# 1_P1_schdoc.net
KiCad netlist of a schematic drawn in Altium Designer
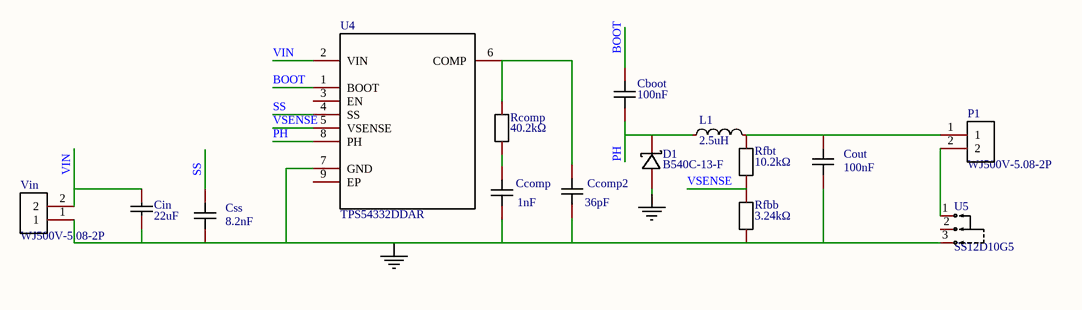
[diagram p0: 1_P1.schdoc.schdoc]

(export (version "E")
  (design (tool "Eeschema 10.0.6"))
  (components
    (comp (ref "Cboot")
      (value "100nF")
      (fields
        (field (name "NAME") "100nF")
        (field (name "MANUFACTURER") "muRata(村田)")
        (field (name "MANUFACTURER PART") "GRM155R71A104KA01D")
        (field (name "TOLERANCE") "±10%")
      )
      (libsource (lib "altium-import") (part "root_1_GRM155R71A104KA01D_"))
    )
    (comp (ref "Ccomp")
      (value "1nF")
      (fields
        (field (name "NAME") "1nF")
        (field (name "MANUFACTURER") "muRata(村田)")
        (field (name "MANUFACTURER PART") "GRM0335C1H360GA01D")
        (field (name "TOLERANCE") "±2%")
      )
      (libsource (lib "altium-import") (part "root_0_GRM0335C1H360GA01D_"))
    )
    (comp (ref "Ccomp2")
      (value "36pF")
      (fields
        (field (name "NAME") "36pF")
        (field (name "MANUFACTURER") "muRata(村田)")
        (field (name "MANUFACTURER PART") "GRM0335C1H360GA01D")
        (field (name "TOLERANCE") "±2%")
      )
      (libsource (lib "altium-import") (part "root_0_GRM0335C1H360GA01D_"))
    )
    (comp (ref "Cin")
      (value "22uF")
      (fields
        (field (name "NAME") "22uF")
        (field (name "MANUFACTURER PART") "GRM32ER61E226KE15L")
        (field (name "MANUFACTURER") "muRata(村田)")
        (field (name "TOLERANCE") "±10%")
      )
      (libsource (lib "altium-import") (part "root_1_GRM32ER61E226KE15L_"))
    )
    (comp (ref "Cout")
      (value "100nF")
      (fields
        (field (name "NAME") "100nF")
        (field (name "MANUFACTURER") "PSA(信昌电陶)")
        (field (name "MANUFACTURER PART") "FE2HX476M500LGL")
        (field (name "TOLERANCE") "±20%")
      )
      (libsource (lib "altium-import") (part "root_1_FE2HX476M500LGL_"))
    )
    (comp (ref "Css")
      (value "8.2nF")
      (fields
        (field (name "NAME") "8.2nF")
        (field (name "MANUFACTURER") "PSA(信昌电陶)")
        (field (name "MANUFACTURER PART") "FE2HX476M500LGL")
        (field (name "TOLERANCE") "±20%")
      )
      (libsource (lib "altium-import") (part "root_1_FE2HX476M500LGL_"))
    )
    (comp (ref "D1")
      (value "B540C-13-F")
      (description "正向压降(Vf):550mV@5A;直流反向耐压(Vr):40V;平均整流电流(Io):5A;")
      (fields (field (name "NAME") "B540C-13-F") (field (name "MANUFACTURER") "DIODES(美台)"))
      (libsource (lib "altium-import") (part "root_3_B540C-13-F_"))
    )
    (comp (ref "L1")
      (value "2.5uH")
      (fields (field (name "NAME") "2.5uH"))
      (libsource (lib "altium-import") (part "root_0_L_0603_"))
    )
    (comp (ref "P1")
      (value "WJ500V-5.08-2P")
      (fields (field (name "NAME") "WJ500V-5.08-2P") (field (name "MANUFACTURER") "KANGNEX(康奈克斯电气)"))
      (libsource (lib "altium-import") (part "root_3_WJ500V-5.08-2P_"))
    )
    (comp (ref "Rcomp")
      (value "40.2kΩ")
      (fields
        (field (name "NAME") "40.2kΩ")
        (field (name "MANUFACTURER") "VISHAY(威世)")
        (field (name "MANUFACTURER PART") "CRCW040240K2FKED")
        (field (name "TOLERANCE") "±1%")
      )
      (libsource (lib "altium-import") (part "root_1_CRCW040240K2FKED_"))
    )
    (comp (ref "Rfbb")
      (value "3.24kΩ")
      (fields
        (field (name "NAME") "3.24kΩ")
        (field (name "MANUFACTURER") "VISHAY(威世)")
        (field (name "MANUFACTURER PART") "CRCW040210K2FKED")
        (field (name "TOLERANCE") "±1%")
      )
      (libsource (lib "altium-import") (part "root_1_CRCW040210K2FKED_"))
    )
    (comp (ref "Rfbt")
      (value "10.2kΩ")
      (fields
        (field (name "NAME") "10.2kΩ")
        (field (name "MANUFACTURER") "VISHAY(威世)")
        (field (name "MANUFACTURER PART") "CRCW040210K2FKED")
        (field (name "TOLERANCE") "±1%")
      )
      (libsource (lib "altium-import") (part "root_1_CRCW040210K2FKED_"))
    )
    (comp (ref "U4")
      (value "TPS54332DDAR")
      (description "功能类型:降压型;输出类型:可调;输入电压:3.5V~28V;输出电压:800mV~26.04V;输出电流(最大值):3.5A;")
      (fields (field (name "NAME") "TPS54332DDAR") (field (name "MANUFACTURER") "TI(德州仪器)"))
      (libsource (lib "altium-import") (part "root_0_TPS54332DDAR_"))
    )
    (comp (ref "U5")
      (value "SS12D10G5")
      (description "电路结构:单刀双掷;安装方式:直插;额定电流(DC):2A;额定电压(DC):125V;机械寿命:3千次;")
      (fields (field (name "NAME") "SS12D10G5") (field (name "MANUFACTURER") "SHOU HAN(首韩)"))
      (libsource (lib "altium-import") (part "root_3_SS12D10G5_"))
    )
    (comp (ref "Vin")
      (value "WJ500V-5.08-2P")
      (fields (field (name "NAME") "WJ500V-5.08-2P") (field (name "MANUFACTURER") "KANGNEX(康奈克斯电气)"))
      (libsource (lib "altium-import") (part "root_1_WJ500V-5.08-2P_"))
    )
  )
  (nets
    (net (code "1") (name "/BOOT") (class "Default")
      (node (ref "Cboot") (pin "2") (pinfunction "2_2") (pintype "passive"))
      (node (ref "U4") (pin "1") (pinfunction "BOOT_1") (pintype "passive"))
    )
    (net (code "2") (name "/PH") (class "Default")
      (node (ref "Cboot") (pin "1") (pinfunction "1_1") (pintype "passive"))
      (node (ref "D1") (pin "1") (pinfunction "K_1") (pintype "passive"))
      (node (ref "L1") (pin "1") (pinfunction "1_1") (pintype "passive"))
      (node (ref "U4") (pin "8") (pinfunction "PH_8") (pintype "passive"))
    )
    (net (code "3") (name "/SS") (class "Default")
      (node (ref "Css") (pin "2") (pinfunction "2_2") (pintype "passive"))
      (node (ref "U4") (pin "4") (pinfunction "SS_4") (pintype "passive"))
    )
    (net (code "4") (name "/VIN") (class "Default")
      (node (ref "Cin") (pin "2") (pinfunction "2_2") (pintype "passive"))
      (node (ref "U4") (pin "2") (pinfunction "VIN_2") (pintype "passive"))
      (node (ref "Vin") (pin "2") (pinfunction "2_2") (pintype "passive"))
    )
    (net (code "5") (name "/VSENSE") (class "Default")
      (node (ref "Rfbb") (pin "2") (pinfunction "2_2") (pintype "passive"))
      (node (ref "Rfbt") (pin "1") (pinfunction "1_1") (pintype "passive"))
      (node (ref "U4") (pin "5") (pinfunction "VSENSE_5") (pintype "passive"))
    )
    (net (code "6") (name "<NO NET>") (class "Default")
      (node (ref "Ccomp") (pin "1") (pinfunction "1_1") (pintype "passive"))
      (node (ref "Ccomp2") (pin "1") (pinfunction "1_1") (pintype "passive"))
      (node (ref "Cin") (pin "1") (pinfunction "1_1") (pintype "passive"))
      (node (ref "Cout") (pin "1") (pinfunction "1_1") (pintype "passive"))
      (node (ref "Css") (pin "1") (pinfunction "1_1") (pintype "passive"))
      (node (ref "D1") (pin "2") (pinfunction "A_2") (pintype "passive"))
      (node (ref "Rfbb") (pin "1") (pinfunction "1_1") (pintype "passive"))
      (node (ref "U4") (pin "7") (pinfunction "GND_7") (pintype "passive"))
      (node (ref "U5") (pin "3") (pinfunction "3_3") (pintype "passive"))
      (node (ref "Vin") (pin "1") (pinfunction "1_1") (pintype "passive"))
    )
    (net (code "7") (name "Net-(Ccomp-Pad2)") (class "Default")
      (node (ref "Ccomp") (pin "2") (pinfunction "2_2") (pintype "passive"))
      (node (ref "Rcomp") (pin "1") (pinfunction "1_1") (pintype "passive"))
    )
    (net (code "8") (name "Net-(Cout-Pad2)") (class "Default")
      (node (ref "Cout") (pin "2") (pinfunction "2_2") (pintype "passive"))
      (node (ref "L1") (pin "2") (pinfunction "2_2") (pintype "passive"))
      (node (ref "P1") (pin "1") (pinfunction "1_1") (pintype "passive"))
      (node (ref "Rfbt") (pin "2") (pinfunction "2_2") (pintype "passive"))
    )
    (net (code "9") (name "Net-(P1-Pad2)") (class "Default")
      (node (ref "P1") (pin "2") (pinfunction "2_2") (pintype "passive"))
      (node (ref "U5") (pin "1") (pinfunction "1_1") (pintype "passive"))
    )
    (net (code "10") (name "Net-(U4-COMP)") (class "Default")
      (node (ref "Ccomp2") (pin "2") (pinfunction "2_2") (pintype "passive"))
      (node (ref "Rcomp") (pin "2") (pinfunction "2_2") (pintype "passive"))
      (node (ref "U4") (pin "6") (pinfunction "COMP_6") (pintype "passive"))
    )
    (net (code "11") (name "unconnected-(U4-EN-Pad3)") (class "Default")
      (node (ref "U4") (pin "3") (pinfunction "EN_3") (pintype "passive"))
    )
    (net (code "12") (name "unconnected-(U4-EP-Pad9)") (class "Default")
      (node (ref "U4") (pin "9") (pinfunction "EP_9") (pintype "passive"))
    )
    (net (code "13") (name "unconnected-(U5-Pad2)") (class "Default")
      (node (ref "U5") (pin "2") (pinfunction "2_2") (pintype "passive"))
    )
  )
)
